# Launch_Tower_Power_Interface_Board_v1-1.net
KiCad netlist of a schematic drawn in EAGLE
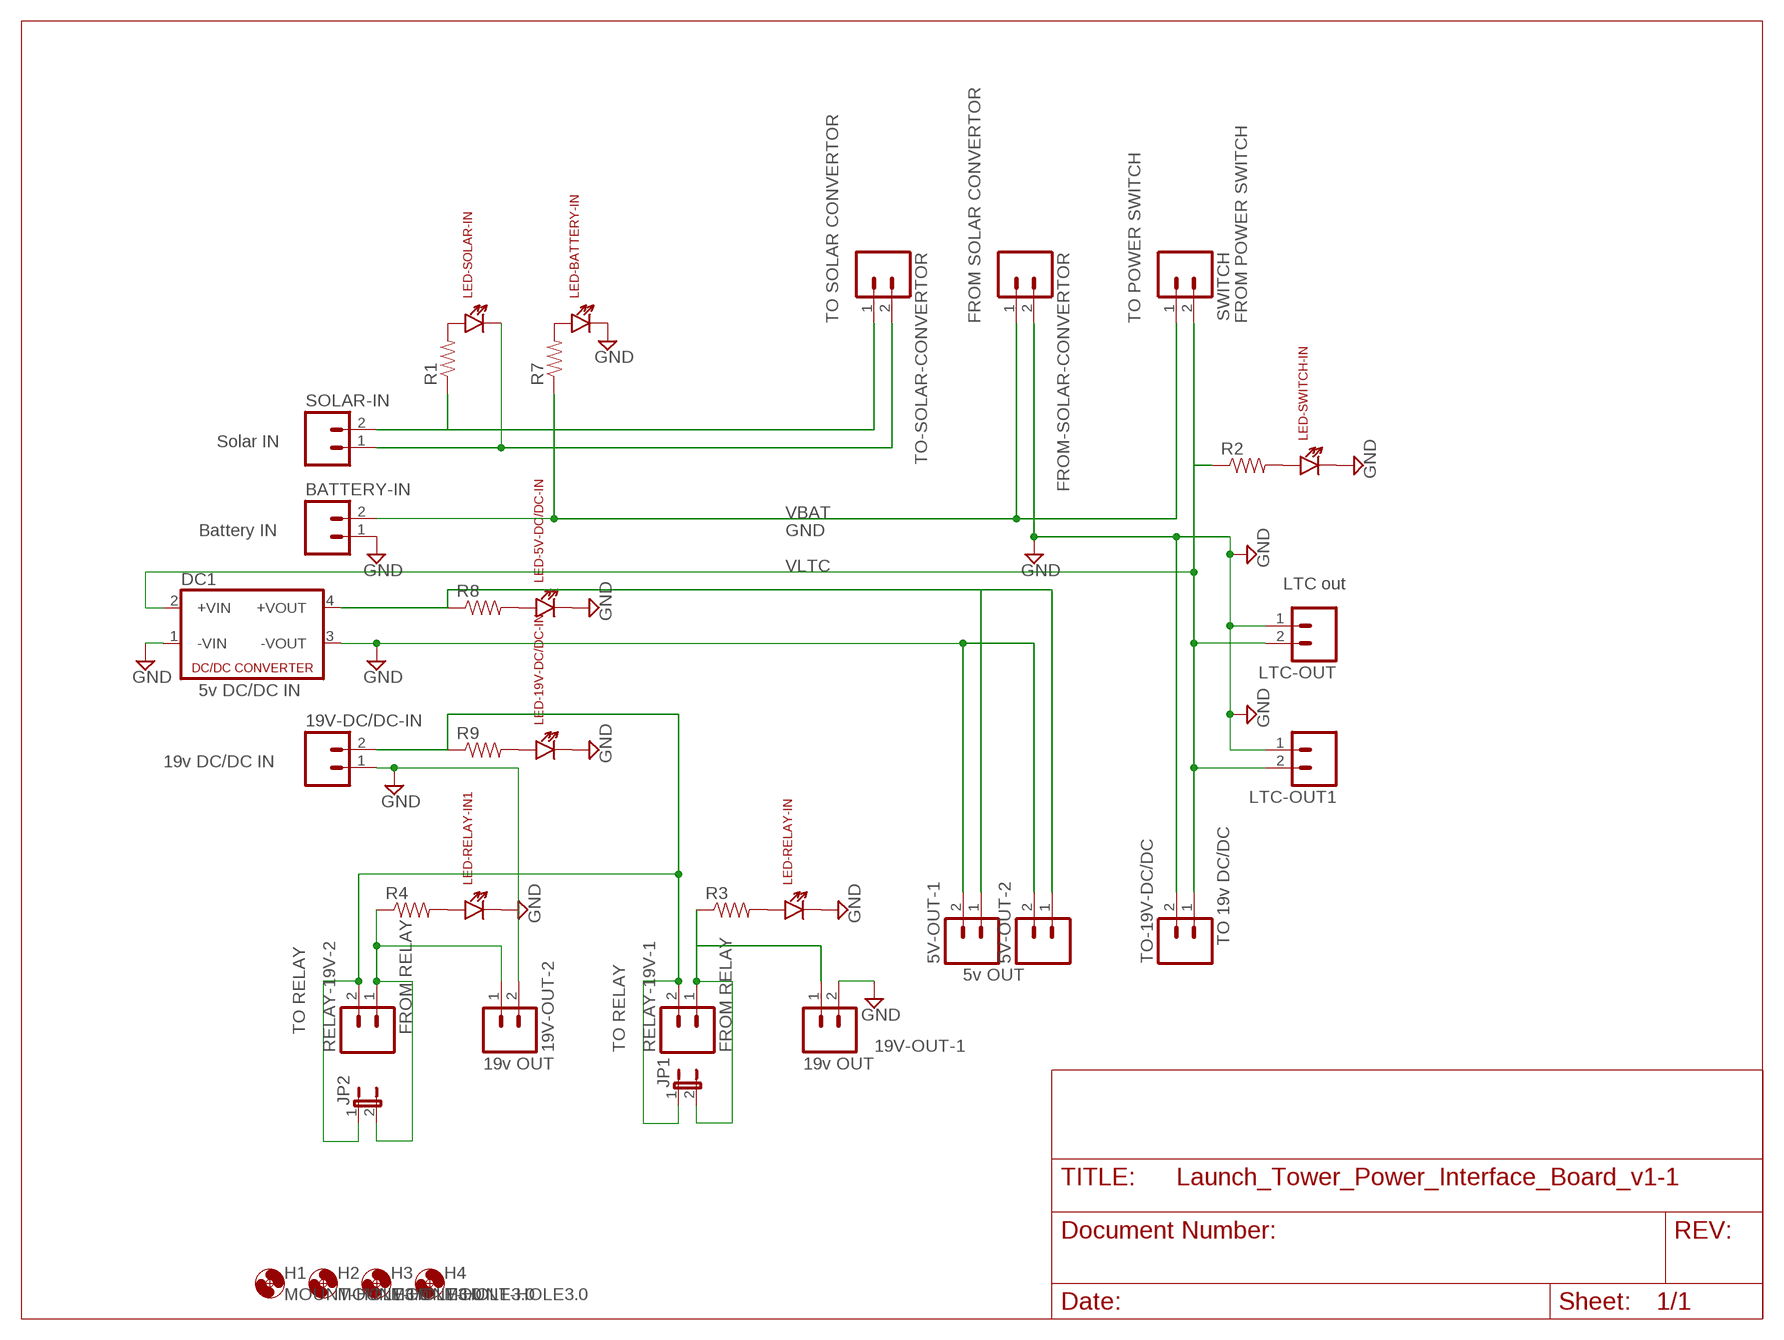
[diagram p0: schematic, sheet 1]

(export (version "E")
  (design (tool "Eeschema 10.0.6"))
  (components
    (comp (ref "5V-OUT-1")
      (value "M023.5MM")
      (footprint "eagle-import:SCREWTERMINAL-3.5MM-2")
      (libsource (lib "eagle-import") (part "M023.5MM"))
    )
    (comp (ref "5V-OUT-2")
      (value "M023.5MM")
      (footprint "eagle-import:SCREWTERMINAL-3.5MM-2")
      (libsource (lib "eagle-import") (part "M023.5MM"))
    )
    (comp (ref "19V-DC/DC-IN")
      (value "M025MM")
      (footprint "eagle-import:SCREWTERMINAL-5MM-2")
      (libsource (lib "eagle-import") (part "M025MM"))
    )
    (comp (ref "19V-OUT-1")
      (value "M025MM")
      (footprint "eagle-import:SCREWTERMINAL-5MM-2")
      (libsource (lib "eagle-import") (part "M025MM"))
    )
    (comp (ref "19V-OUT-2")
      (value "M025MM")
      (footprint "eagle-import:SCREWTERMINAL-5MM-2")
      (libsource (lib "eagle-import") (part "M025MM"))
    )
    (comp (ref "BATTERY-IN")
      (value "M025MM")
      (footprint "eagle-import:SCREWTERMINAL-5MM-2")
      (libsource (lib "eagle-import") (part "M025MM"))
    )
    (comp (ref "DC1")
      (value "NME")
      (footprint "eagle-import:NME")
      (fields (field (name "MF") "C & D TECHNOLOGIES, INC") (field (name "MPN") "NME1205D"))
      (libsource (lib "eagle-import") (part "NME"))
    )
    (comp (ref "FROM-SOLAR-CONVERTOR")
      (value "M025MM")
      (footprint "eagle-import:SCREWTERMINAL-5MM-2")
      (libsource (lib "eagle-import") (part "M025MM"))
    )
    (comp (ref "H1")
      (value "MOUNT-HOLE3.0")
      (footprint "eagle-import:3,0")
      (libsource (lib "eagle-import") (part "MOUNT-HOLE3.0"))
    )
    (comp (ref "H2")
      (value "MOUNT-HOLE3.0")
      (footprint "eagle-import:3,0")
      (libsource (lib "eagle-import") (part "MOUNT-HOLE3.0"))
    )
    (comp (ref "H3")
      (value "MOUNT-HOLE3.0")
      (footprint "eagle-import:3,0")
      (libsource (lib "eagle-import") (part "MOUNT-HOLE3.0"))
    )
    (comp (ref "H4")
      (value "MOUNT-HOLE3.0")
      (footprint "eagle-import:3,0")
      (libsource (lib "eagle-import") (part "MOUNT-HOLE3.0"))
    )
    (comp (ref "JP1")
      (value "JUMPER-2PTH")
      (footprint "eagle-import:1X02")
      (libsource (lib "eagle-import") (part "JUMPER-2PTH"))
    )
    (comp (ref "JP2")
      (value "JUMPER-2PTH")
      (footprint "eagle-import:1X02")
      (libsource (lib "eagle-import") (part "JUMPER-2PTH"))
    )
    (comp (ref "LED-5V-DC/DC-IN")
      (value "LTE-302")
      (footprint "eagle-import:LTE-302")
      (libsource (lib "eagle-import") (part "LTE-302"))
    )
    (comp (ref "LED-19V-DC/DC-IN")
      (value "LTE-302")
      (footprint "eagle-import:LTE-302")
      (libsource (lib "eagle-import") (part "LTE-302"))
    )
    (comp (ref "LED-BATTERY-IN")
      (value "LTE-302")
      (footprint "eagle-import:LTE-302")
      (libsource (lib "eagle-import") (part "LTE-302"))
    )
    (comp (ref "LED-RELAY-IN")
      (value "LTE-302")
      (footprint "eagle-import:LTE-302")
      (libsource (lib "eagle-import") (part "LTE-302"))
    )
    (comp (ref "LED-RELAY-IN1")
      (value "LTE-302")
      (footprint "eagle-import:LTE-302")
      (libsource (lib "eagle-import") (part "LTE-302"))
    )
    (comp (ref "LED-SOLAR-IN")
      (value "LTE-302")
      (footprint "eagle-import:LTE-302")
      (libsource (lib "eagle-import") (part "LTE-302"))
    )
    (comp (ref "LED-SWITCH-IN")
      (value "LTE-302")
      (footprint "eagle-import:LTE-302")
      (libsource (lib "eagle-import") (part "LTE-302"))
    )
    (comp (ref "LTC-OUT")
      (value "M025MM")
      (footprint "eagle-import:SCREWTERMINAL-5MM-2")
      (libsource (lib "eagle-import") (part "M025MM"))
    )
    (comp (ref "LTC-OUT1")
      (value "M025MM")
      (footprint "eagle-import:SCREWTERMINAL-5MM-2")
      (libsource (lib "eagle-import") (part "M025MM"))
    )
    (comp (ref "R1")
      (value "RESISTORPTH-1/2W")
      (footprint "eagle-import:AXIAL-0.5")
      (libsource (lib "eagle-import") (part "RESISTORPTH-1/2W"))
    )
    (comp (ref "R2")
      (value "RESISTORPTH-1/2W")
      (footprint "eagle-import:AXIAL-0.5")
      (libsource (lib "eagle-import") (part "RESISTORPTH-1/2W"))
    )
    (comp (ref "R3")
      (value "RESISTORPTH-1/2W")
      (footprint "eagle-import:AXIAL-0.5")
      (libsource (lib "eagle-import") (part "RESISTORPTH-1/2W"))
    )
    (comp (ref "R4")
      (value "RESISTORPTH-1/2W")
      (footprint "eagle-import:AXIAL-0.5")
      (libsource (lib "eagle-import") (part "RESISTORPTH-1/2W"))
    )
    (comp (ref "R7")
      (value "RESISTORPTH-1/2W")
      (footprint "eagle-import:AXIAL-0.5")
      (libsource (lib "eagle-import") (part "RESISTORPTH-1/2W"))
    )
    (comp (ref "R8")
      (value "RESISTORPTH-1/2W")
      (footprint "eagle-import:AXIAL-0.5")
      (libsource (lib "eagle-import") (part "RESISTORPTH-1/2W"))
    )
    (comp (ref "R9")
      (value "RESISTORPTH-1/2W")
      (footprint "eagle-import:AXIAL-0.5")
      (libsource (lib "eagle-import") (part "RESISTORPTH-1/2W"))
    )
    (comp (ref "RELAY-19V-1")
      (value "M025MM")
      (footprint "eagle-import:SCREWTERMINAL-5MM-2")
      (libsource (lib "eagle-import") (part "M025MM"))
    )
    (comp (ref "RELAY-19V-2")
      (value "M025MM")
      (footprint "eagle-import:SCREWTERMINAL-5MM-2")
      (libsource (lib "eagle-import") (part "M025MM"))
    )
    (comp (ref "SOLAR-IN")
      (value "M025MM")
      (footprint "eagle-import:SCREWTERMINAL-5MM-2")
      (libsource (lib "eagle-import") (part "M025MM"))
    )
    (comp (ref "SWITCH")
      (value "M025MM")
      (footprint "eagle-import:SCREWTERMINAL-5MM-2")
      (libsource (lib "eagle-import") (part "M025MM"))
    )
    (comp (ref "TO-19V-DC/DC")
      (value "M025MM")
      (footprint "eagle-import:SCREWTERMINAL-5MM-2")
      (libsource (lib "eagle-import") (part "M025MM"))
    )
    (comp (ref "TO-SOLAR-CONVERTOR")
      (value "M025MM")
      (footprint "eagle-import:SCREWTERMINAL-5MM-2")
      (libsource (lib "eagle-import") (part "M025MM"))
    )
  )
  (nets
    (net (code "1") (name "/VBAT") (class "Default")
      (node (ref "BATTERY-IN") (pin "2") (pinfunction "2_2") (pintype "passive"))
      (node (ref "FROM-SOLAR-CONVERTOR") (pin "1") (pinfunction "1_1") (pintype "passive"))
      (node (ref "R7") (pin "P$1") (pinfunction "1_P$1") (pintype "passive"))
      (node (ref "SWITCH") (pin "1") (pinfunction "1_1") (pintype "passive"))
    )
    (net (code "2") (name "/VLTC") (class "Default")
      (node (ref "DC1") (pin "2") (pinfunction "+VIN_2") (pintype "passive"))
      (node (ref "LTC-OUT") (pin "2") (pinfunction "2_2") (pintype "passive"))
      (node (ref "LTC-OUT1") (pin "2") (pinfunction "2_2") (pintype "passive"))
      (node (ref "R2") (pin "P$1") (pinfunction "1_P$1") (pintype "passive"))
      (node (ref "SWITCH") (pin "2") (pinfunction "2_2") (pintype "passive"))
      (node (ref "TO-19V-DC/DC") (pin "1") (pinfunction "1_1") (pintype "passive"))
    )
    (net (code "3") (name "GND") (class "Default")
      (node (ref "19V-DC/DC-IN") (pin "1") (pinfunction "1_1") (pintype "passive"))
      (node (ref "19V-OUT-1") (pin "2") (pinfunction "2_2") (pintype "passive"))
      (node (ref "19V-OUT-2") (pin "2") (pinfunction "2_2") (pintype "passive"))
      (node (ref "5V-OUT-1") (pin "2") (pinfunction "2_2") (pintype "passive"))
      (node (ref "5V-OUT-2") (pin "2") (pinfunction "2_2") (pintype "passive"))
      (node (ref "BATTERY-IN") (pin "1") (pinfunction "1_1") (pintype "passive"))
      (node (ref "DC1") (pin "1") (pinfunction "-VIN_1") (pintype "passive"))
      (node (ref "DC1") (pin "3") (pinfunction "-VOUT_3") (pintype "passive"))
      (node (ref "FROM-SOLAR-CONVERTOR") (pin "2") (pinfunction "2_2") (pintype "passive"))
      (node (ref "LED-19V-DC/DC-IN") (pin "C") (pinfunction "C_C") (pintype "bidirectional"))
      (node (ref "LED-5V-DC/DC-IN") (pin "C") (pinfunction "C_C") (pintype "bidirectional"))
      (node (ref "LED-BATTERY-IN") (pin "C") (pinfunction "C_C") (pintype "bidirectional"))
      (node (ref "LED-RELAY-IN") (pin "C") (pinfunction "C_C") (pintype "bidirectional"))
      (node (ref "LED-RELAY-IN1") (pin "C") (pinfunction "C_C") (pintype "bidirectional"))
      (node (ref "LED-SWITCH-IN") (pin "C") (pinfunction "C_C") (pintype "bidirectional"))
      (node (ref "LTC-OUT") (pin "1") (pinfunction "1_1") (pintype "passive"))
      (node (ref "LTC-OUT1") (pin "1") (pinfunction "1_1") (pintype "passive"))
      (node (ref "TO-19V-DC/DC") (pin "2") (pinfunction "2_2") (pintype "passive"))
    )
    (net (code "4") (name "Net-(DC1-+VOUT)") (class "Default")
      (node (ref "5V-OUT-1") (pin "1") (pinfunction "1_1") (pintype "passive"))
      (node (ref "5V-OUT-2") (pin "1") (pinfunction "1_1") (pintype "passive"))
      (node (ref "DC1") (pin "4") (pinfunction "+VOUT_4") (pintype "passive"))
      (node (ref "R8") (pin "P$1") (pinfunction "1_P$1") (pintype "passive"))
    )
    (net (code "5") (name "Net-(LED-SOLAR-IN-PadC)") (class "Default")
      (node (ref "LED-SOLAR-IN") (pin "C") (pinfunction "C_C") (pintype "bidirectional"))
      (node (ref "SOLAR-IN") (pin "1") (pinfunction "1_1") (pintype "passive"))
      (node (ref "TO-SOLAR-CONVERTOR") (pin "2") (pinfunction "2_2") (pintype "passive"))
    )
    (net (code "6") (name "Net-(R1-1)") (class "Default")
      (node (ref "R1") (pin "P$1") (pinfunction "1_P$1") (pintype "passive"))
      (node (ref "SOLAR-IN") (pin "2") (pinfunction "2_2") (pintype "passive"))
      (node (ref "TO-SOLAR-CONVERTOR") (pin "1") (pinfunction "1_1") (pintype "passive"))
    )
    (net (code "7") (name "Net-(R1-2)") (class "Default")
      (node (ref "LED-SOLAR-IN") (pin "A") (pinfunction "A_A") (pintype "bidirectional"))
      (node (ref "R1") (pin "P$2") (pinfunction "2_P$2") (pintype "passive"))
    )
    (net (code "8") (name "Net-(R2-2)") (class "Default")
      (node (ref "LED-SWITCH-IN") (pin "A") (pinfunction "A_A") (pintype "bidirectional"))
      (node (ref "R2") (pin "P$2") (pinfunction "2_P$2") (pintype "passive"))
    )
    (net (code "9") (name "Net-(R3-1)") (class "Default")
      (node (ref "19V-OUT-1") (pin "1") (pinfunction "1_1") (pintype "passive"))
      (node (ref "JP1") (pin "2") (pinfunction "2_2") (pintype "passive"))
      (node (ref "R3") (pin "P$1") (pinfunction "1_P$1") (pintype "passive"))
      (node (ref "RELAY-19V-1") (pin "1") (pinfunction "1_1") (pintype "passive"))
    )
    (net (code "10") (name "Net-(R3-2)") (class "Default")
      (node (ref "LED-RELAY-IN") (pin "A") (pinfunction "A_A") (pintype "bidirectional"))
      (node (ref "R3") (pin "P$2") (pinfunction "2_P$2") (pintype "passive"))
    )
    (net (code "11") (name "Net-(R4-1)") (class "Default")
      (node (ref "19V-OUT-2") (pin "1") (pinfunction "1_1") (pintype "passive"))
      (node (ref "JP2") (pin "2") (pinfunction "2_2") (pintype "passive"))
      (node (ref "R4") (pin "P$1") (pinfunction "1_P$1") (pintype "passive"))
      (node (ref "RELAY-19V-2") (pin "1") (pinfunction "1_1") (pintype "passive"))
    )
    (net (code "12") (name "Net-(R4-2)") (class "Default")
      (node (ref "LED-RELAY-IN1") (pin "A") (pinfunction "A_A") (pintype "bidirectional"))
      (node (ref "R4") (pin "P$2") (pinfunction "2_P$2") (pintype "passive"))
    )
    (net (code "13") (name "Net-(R7-2)") (class "Default")
      (node (ref "LED-BATTERY-IN") (pin "A") (pinfunction "A_A") (pintype "bidirectional"))
      (node (ref "R7") (pin "P$2") (pinfunction "2_P$2") (pintype "passive"))
    )
    (net (code "14") (name "Net-(R8-2)") (class "Default")
      (node (ref "LED-5V-DC/DC-IN") (pin "A") (pinfunction "A_A") (pintype "bidirectional"))
      (node (ref "R8") (pin "P$2") (pinfunction "2_P$2") (pintype "passive"))
    )
    (net (code "15") (name "Net-(R9-1)") (class "Default")
      (node (ref "19V-DC/DC-IN") (pin "2") (pinfunction "2_2") (pintype "passive"))
      (node (ref "JP1") (pin "1") (pinfunction "1_1") (pintype "passive"))
      (node (ref "JP2") (pin "1") (pinfunction "1_1") (pintype "passive"))
      (node (ref "R9") (pin "P$1") (pinfunction "1_P$1") (pintype "passive"))
      (node (ref "RELAY-19V-1") (pin "2") (pinfunction "2_2") (pintype "passive"))
      (node (ref "RELAY-19V-2") (pin "2") (pinfunction "2_2") (pintype "passive"))
    )
    (net (code "16") (name "Net-(R9-2)") (class "Default")
      (node (ref "LED-19V-DC/DC-IN") (pin "A") (pinfunction "A_A") (pintype "bidirectional"))
      (node (ref "R9") (pin "P$2") (pinfunction "2_P$2") (pintype "passive"))
    )
  )
)
